# TIVA_2.net
KiCad netlist of a schematic drawn in Altium Designer
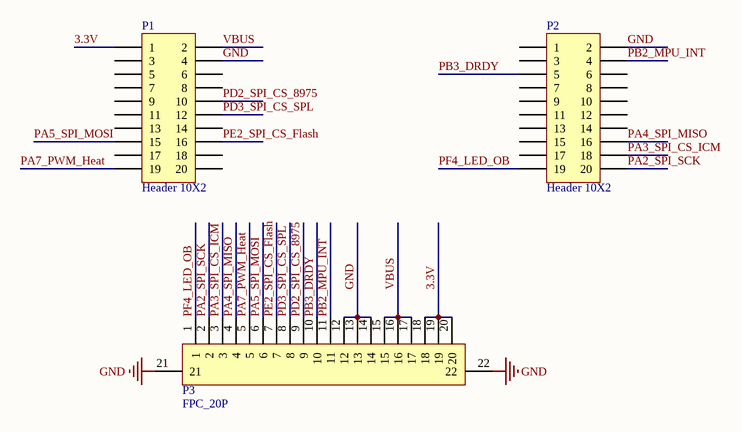
[diagram p0: TIVA_2.SchDoc]

(export (version "E")
  (design (tool "Eeschema 10.0.6"))
  (components
    (comp (ref "P1")
      (value "Header 10X2")
      (footprint "HDR2X10")
      (description "Header, 10-Pin, Dual row")
      (fields (field (name "PUBLISHER") "Altium Limited"))
      (libsource (lib "TIVALib") (part "Header 10X2"))
    )
    (comp (ref "P2")
      (value "Header 10X2")
      (footprint "HDR2X10")
      (description "Header, 10-Pin, Dual row")
      (fields (field (name "PUBLISHER") "Altium Limited"))
      (libsource (lib "TIVALib") (part "Header 10X2"))
    )
    (comp (ref "P3") (value "FPC_20P") (footprint "FPC1.0_20P") (libsource (lib "TIVALib") (part "FPC_20P")))
  )
  (nets
    (net (code "1") (name "/3.3V") (class "Default")
      (node (ref "P1") (pin "1") (pinfunction "1_1") (pintype "passive"))
      (node (ref "P3") (pin "18") (pinfunction "18_18") (pintype "passive"))
      (node (ref "P3") (pin "19") (pinfunction "19_19") (pintype "passive"))
      (node (ref "P3") (pin "20") (pinfunction "20_20") (pintype "passive"))
    )
    (net (code "3") (name "/PA2_SPI_SCK") (class "Default")
      (node (ref "P2") (pin "20") (pinfunction "20_20") (pintype "passive"))
      (node (ref "P3") (pin "2") (pinfunction "2_2") (pintype "passive"))
    )
    (net (code "4") (name "/PA3_SPI_CS_ICM") (class "Default")
      (node (ref "P2") (pin "18") (pinfunction "18_18") (pintype "passive"))
      (node (ref "P3") (pin "3") (pinfunction "3_3") (pintype "passive"))
    )
    (net (code "5") (name "/PA4_SPI_MISO") (class "Default")
      (node (ref "P2") (pin "16") (pinfunction "16_16") (pintype "passive"))
      (node (ref "P3") (pin "4") (pinfunction "4_4") (pintype "passive"))
    )
    (net (code "6") (name "/PA5_SPI_MOSI") (class "Default")
      (node (ref "P1") (pin "15") (pinfunction "15_15") (pintype "passive"))
      (node (ref "P3") (pin "6") (pinfunction "6_6") (pintype "passive"))
    )
    (net (code "7") (name "/PA7_PWM_Heat") (class "Default")
      (node (ref "P1") (pin "19") (pinfunction "19_19") (pintype "passive"))
      (node (ref "P3") (pin "5") (pinfunction "5_5") (pintype "passive"))
    )
    (net (code "8") (name "/PB2_MPU_INT") (class "Default")
      (node (ref "P2") (pin "4") (pinfunction "4_4") (pintype "passive"))
      (node (ref "P3") (pin "11") (pinfunction "11_11") (pintype "passive"))
    )
    (net (code "9") (name "/PB3_DRDY") (class "Default")
      (node (ref "P2") (pin "5") (pinfunction "5_5") (pintype "passive"))
      (node (ref "P3") (pin "10") (pinfunction "10_10") (pintype "passive"))
    )
    (net (code "10") (name "/PD2_SPI_CS_8975") (class "Default")
      (node (ref "P1") (pin "10") (pinfunction "10_10") (pintype "passive"))
      (node (ref "P3") (pin "9") (pinfunction "9_9") (pintype "passive"))
    )
    (net (code "11") (name "/PD3_SPI_CS_SPL") (class "Default")
      (node (ref "P1") (pin "12") (pinfunction "12_12") (pintype "passive"))
      (node (ref "P3") (pin "8") (pinfunction "8_8") (pintype "passive"))
    )
    (net (code "12") (name "/PE2_SPI_CS_Flash") (class "Default")
      (node (ref "P1") (pin "16") (pinfunction "16_16") (pintype "passive"))
      (node (ref "P3") (pin "7") (pinfunction "7_7") (pintype "passive"))
    )
    (net (code "13") (name "/PF4_LED_OB") (class "Default")
      (node (ref "P2") (pin "19") (pinfunction "19_19") (pintype "passive"))
      (node (ref "P3") (pin "1") (pinfunction "1_1") (pintype "passive"))
    )
    (net (code "14") (name "/VBUS") (class "Default")
      (node (ref "P1") (pin "2") (pinfunction "2_2") (pintype "passive"))
      (node (ref "P3") (pin "15") (pinfunction "15_15") (pintype "passive"))
      (node (ref "P3") (pin "16") (pinfunction "16_16") (pintype "passive"))
      (node (ref "P3") (pin "17") (pinfunction "17_17") (pintype "passive"))
    )
    (net (code "15") (name "GND") (class "Default")
      (node (ref "P1") (pin "4") (pinfunction "4_4") (pintype "passive"))
      (node (ref "P2") (pin "2") (pinfunction "2_2") (pintype "passive"))
      (node (ref "P3") (pin "12") (pinfunction "12_12") (pintype "passive"))
      (node (ref "P3") (pin "13") (pinfunction "13_13") (pintype "passive"))
      (node (ref "P3") (pin "14") (pinfunction "14_14") (pintype "passive"))
      (node (ref "P3") (pin "21") (pinfunction "21_21") (pintype "passive"))
      (node (ref "P3") (pin "22") (pinfunction "22_22") (pintype "passive"))
    )
    (net (code "16") (name "unconnected-(P1-Pad3)") (class "Default")
      (node (ref "P1") (pin "3") (pinfunction "3_3") (pintype "passive"))
    )
    (net (code "17") (name "unconnected-(P1-Pad5)") (class "Default")
      (node (ref "P1") (pin "5") (pinfunction "5_5") (pintype "passive"))
    )
    (net (code "18") (name "unconnected-(P1-Pad6)") (class "Default")
      (node (ref "P1") (pin "6") (pinfunction "6_6") (pintype "passive"))
    )
    (net (code "19") (name "unconnected-(P1-Pad7)") (class "Default")
      (node (ref "P1") (pin "7") (pinfunction "7_7") (pintype "passive"))
    )
    (net (code "20") (name "unconnected-(P1-Pad8)") (class "Default")
      (node (ref "P1") (pin "8") (pinfunction "8_8") (pintype "passive"))
    )
    (net (code "21") (name "unconnected-(P1-Pad9)") (class "Default")
      (node (ref "P1") (pin "9") (pinfunction "9_9") (pintype "passive"))
    )
    (net (code "22") (name "unconnected-(P1-Pad11)") (class "Default")
      (node (ref "P1") (pin "11") (pinfunction "11_11") (pintype "passive"))
    )
    (net (code "23") (name "unconnected-(P1-Pad13)") (class "Default")
      (node (ref "P1") (pin "13") (pinfunction "13_13") (pintype "passive"))
    )
    (net (code "24") (name "unconnected-(P1-Pad14)") (class "Default")
      (node (ref "P1") (pin "14") (pinfunction "14_14") (pintype "passive"))
    )
    (net (code "25") (name "unconnected-(P1-Pad17)") (class "Default")
      (node (ref "P1") (pin "17") (pinfunction "17_17") (pintype "passive"))
    )
    (net (code "26") (name "unconnected-(P1-Pad18)") (class "Default")
      (node (ref "P1") (pin "18") (pinfunction "18_18") (pintype "passive"))
    )
    (net (code "27") (name "unconnected-(P1-Pad20)") (class "Default")
      (node (ref "P1") (pin "20") (pinfunction "20_20") (pintype "passive"))
    )
    (net (code "28") (name "unconnected-(P2-Pad1)") (class "Default")
      (node (ref "P2") (pin "1") (pinfunction "1_1") (pintype "passive"))
    )
    (net (code "29") (name "unconnected-(P2-Pad3)") (class "Default")
      (node (ref "P2") (pin "3") (pinfunction "3_3") (pintype "passive"))
    )
    (net (code "30") (name "unconnected-(P2-Pad6)") (class "Default")
      (node (ref "P2") (pin "6") (pinfunction "6_6") (pintype "passive"))
    )
    (net (code "31") (name "unconnected-(P2-Pad7)") (class "Default")
      (node (ref "P2") (pin "7") (pinfunction "7_7") (pintype "passive"))
    )
    (net (code "32") (name "unconnected-(P2-Pad8)") (class "Default")
      (node (ref "P2") (pin "8") (pinfunction "8_8") (pintype "passive"))
    )
    (net (code "33") (name "unconnected-(P2-Pad9)") (class "Default")
      (node (ref "P2") (pin "9") (pinfunction "9_9") (pintype "passive"))
    )
    (net (code "34") (name "unconnected-(P2-Pad10)") (class "Default")
      (node (ref "P2") (pin "10") (pinfunction "10_10") (pintype "passive"))
    )
    (net (code "35") (name "unconnected-(P2-Pad11)") (class "Default")
      (node (ref "P2") (pin "11") (pinfunction "11_11") (pintype "passive"))
    )
    (net (code "36") (name "unconnected-(P2-Pad12)") (class "Default")
      (node (ref "P2") (pin "12") (pinfunction "12_12") (pintype "passive"))
    )
    (net (code "37") (name "unconnected-(P2-Pad13)") (class "Default")
      (node (ref "P2") (pin "13") (pinfunction "13_13") (pintype "passive"))
    )
    (net (code "38") (name "unconnected-(P2-Pad14)") (class "Default")
      (node (ref "P2") (pin "14") (pinfunction "14_14") (pintype "passive"))
    )
    (net (code "39") (name "unconnected-(P2-Pad15)") (class "Default")
      (node (ref "P2") (pin "15") (pinfunction "15_15") (pintype "passive"))
    )
    (net (code "40") (name "unconnected-(P2-Pad17)") (class "Default")
      (node (ref "P2") (pin "17") (pinfunction "17_17") (pintype "passive"))
    )
  )
)
